# TopSide.net
KiCad netlist of a schematic drawn in Altium Designer
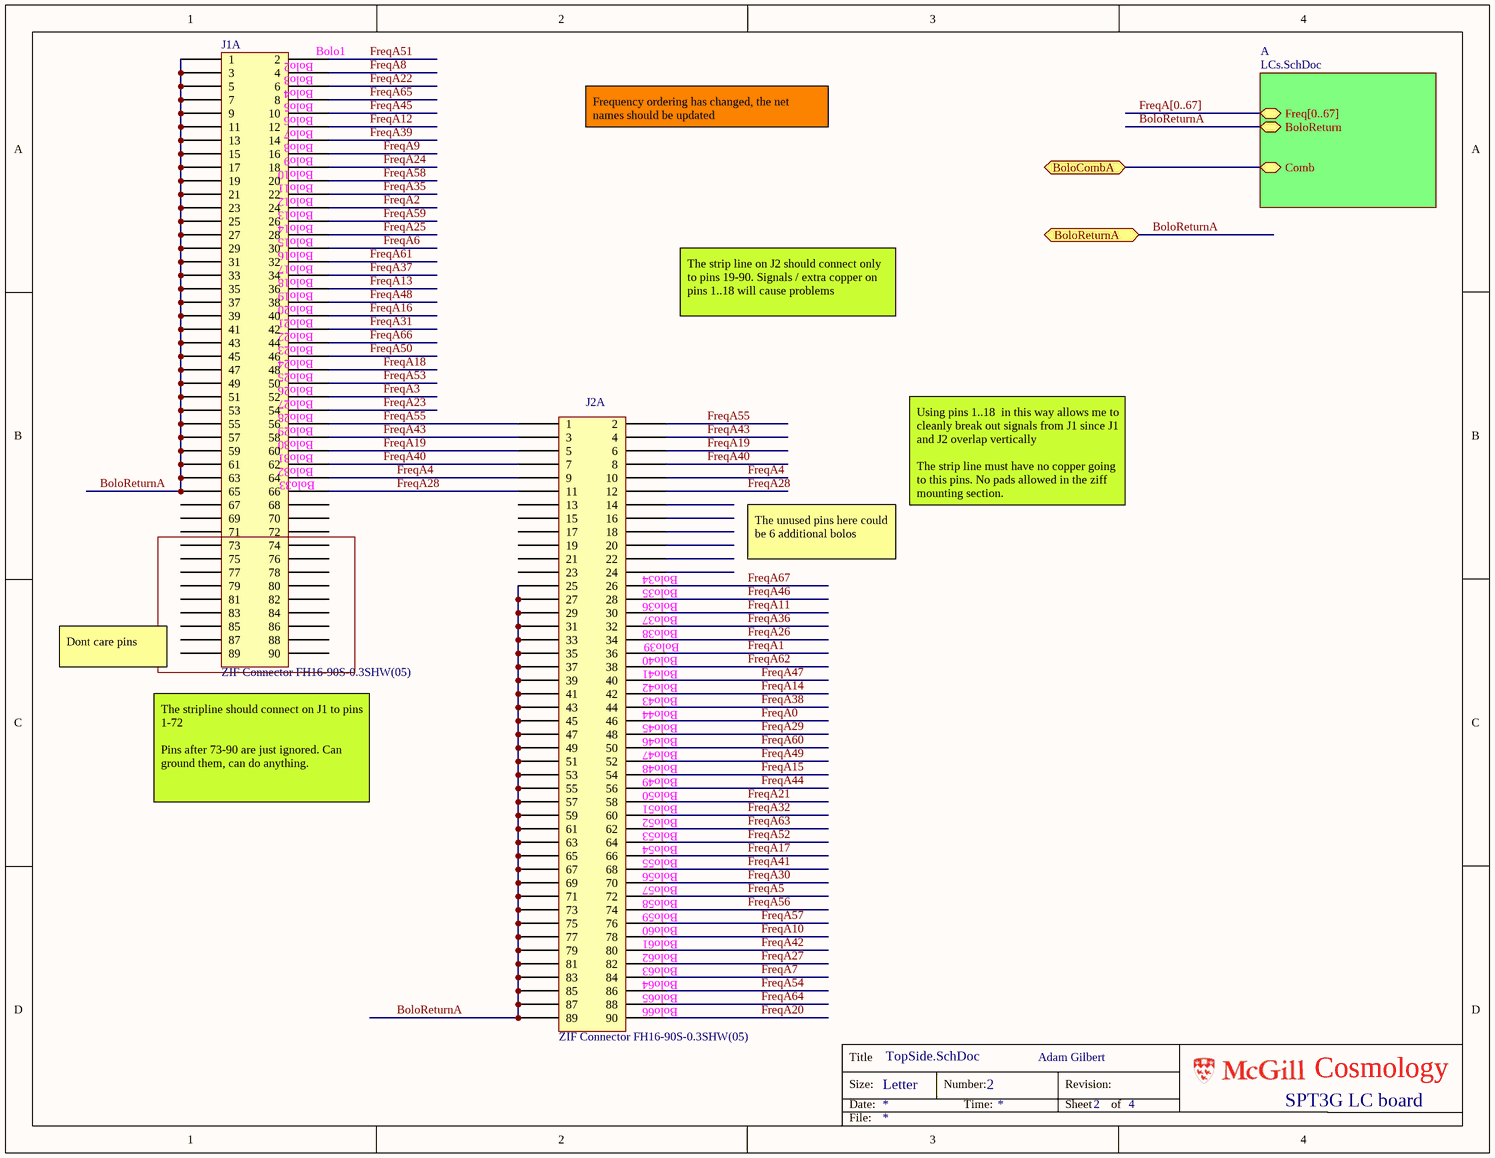
[diagram p0: TopSide.SchDoc]

(export (version "E")
  (design (tool "Eeschema 10.0.6"))
  (components
    (comp (ref "J1A")
      (value "ZIF Connector FH16-90S-0.3SHW(05)")
      (footprint "LCBoard_ZIFCon")
      (libsource (lib "SPT3G_LCBoard") (part "LCboard_FH16-90S-0.3SHW(05)"))
    )
    (comp (ref "J2A")
      (value "ZIF Connector FH16-90S-0.3SHW(05)")
      (footprint "LCBoard_ZIFCon")
      (libsource (lib "SPT3G_LCBoard") (part "LCboard_FH16-90S-0.3SHW(05)"))
    )
  )
  (nets
    (net (code "4") (name "/BoloReturnA") (class "Default")
      (node (ref "J1A") (pin "1") (pinfunction "1_1") (pintype "passive"))
      (node (ref "J1A") (pin "11") (pinfunction "11_11") (pintype "passive"))
      (node (ref "J1A") (pin "13") (pinfunction "13_13") (pintype "passive"))
      (node (ref "J1A") (pin "15") (pinfunction "15_15") (pintype "passive"))
      (node (ref "J1A") (pin "17") (pinfunction "17_17") (pintype "passive"))
      (node (ref "J1A") (pin "19") (pinfunction "19_19") (pintype "passive"))
      (node (ref "J1A") (pin "21") (pinfunction "21_21") (pintype "passive"))
      (node (ref "J1A") (pin "23") (pinfunction "23_23") (pintype "passive"))
      (node (ref "J1A") (pin "25") (pinfunction "25_25") (pintype "passive"))
      (node (ref "J1A") (pin "27") (pinfunction "27_27") (pintype "passive"))
      (node (ref "J1A") (pin "29") (pinfunction "29_29") (pintype "passive"))
      (node (ref "J1A") (pin "3") (pinfunction "3_3") (pintype "passive"))
      (node (ref "J1A") (pin "31") (pinfunction "31_31") (pintype "passive"))
      (node (ref "J1A") (pin "33") (pinfunction "33_33") (pintype "passive"))
      (node (ref "J1A") (pin "35") (pinfunction "35_35") (pintype "passive"))
      (node (ref "J1A") (pin "37") (pinfunction "37_37") (pintype "passive"))
      (node (ref "J1A") (pin "39") (pinfunction "39_39") (pintype "passive"))
      (node (ref "J1A") (pin "41") (pinfunction "41_41") (pintype "passive"))
      (node (ref "J1A") (pin "43") (pinfunction "43_43") (pintype "passive"))
      (node (ref "J1A") (pin "45") (pinfunction "45_45") (pintype "passive"))
      (node (ref "J1A") (pin "47") (pinfunction "47_47") (pintype "passive"))
      (node (ref "J1A") (pin "49") (pinfunction "49_49") (pintype "passive"))
      (node (ref "J1A") (pin "5") (pinfunction "5_5") (pintype "passive"))
      (node (ref "J1A") (pin "51") (pinfunction "51_51") (pintype "passive"))
      (node (ref "J1A") (pin "53") (pinfunction "53_53") (pintype "passive"))
      (node (ref "J1A") (pin "55") (pinfunction "55_55") (pintype "passive"))
      (node (ref "J1A") (pin "57") (pinfunction "57_57") (pintype "passive"))
      (node (ref "J1A") (pin "59") (pinfunction "59_59") (pintype "passive"))
      (node (ref "J1A") (pin "61") (pinfunction "61_61") (pintype "passive"))
      (node (ref "J1A") (pin "63") (pinfunction "63_63") (pintype "passive"))
      (node (ref "J1A") (pin "65") (pinfunction "65_65") (pintype "passive"))
      (node (ref "J1A") (pin "7") (pinfunction "7_7") (pintype "passive"))
      (node (ref "J1A") (pin "9") (pinfunction "9_9") (pintype "passive"))
      (node (ref "J2A") (pin "25") (pinfunction "25_25") (pintype "passive"))
      (node (ref "J2A") (pin "27") (pinfunction "27_27") (pintype "passive"))
      (node (ref "J2A") (pin "29") (pinfunction "29_29") (pintype "passive"))
      (node (ref "J2A") (pin "31") (pinfunction "31_31") (pintype "passive"))
      (node (ref "J2A") (pin "33") (pinfunction "33_33") (pintype "passive"))
      (node (ref "J2A") (pin "35") (pinfunction "35_35") (pintype "passive"))
      (node (ref "J2A") (pin "37") (pinfunction "37_37") (pintype "passive"))
      (node (ref "J2A") (pin "39") (pinfunction "39_39") (pintype "passive"))
      (node (ref "J2A") (pin "41") (pinfunction "41_41") (pintype "passive"))
      (node (ref "J2A") (pin "43") (pinfunction "43_43") (pintype "passive"))
      (node (ref "J2A") (pin "45") (pinfunction "45_45") (pintype "passive"))
      (node (ref "J2A") (pin "47") (pinfunction "47_47") (pintype "passive"))
      (node (ref "J2A") (pin "49") (pinfunction "49_49") (pintype "passive"))
      (node (ref "J2A") (pin "51") (pinfunction "51_51") (pintype "passive"))
      (node (ref "J2A") (pin "53") (pinfunction "53_53") (pintype "passive"))
      (node (ref "J2A") (pin "55") (pinfunction "55_55") (pintype "passive"))
      (node (ref "J2A") (pin "57") (pinfunction "57_57") (pintype "passive"))
      (node (ref "J2A") (pin "59") (pinfunction "59_59") (pintype "passive"))
      (node (ref "J2A") (pin "61") (pinfunction "61_61") (pintype "passive"))
      (node (ref "J2A") (pin "63") (pinfunction "63_63") (pintype "passive"))
      (node (ref "J2A") (pin "65") (pinfunction "65_65") (pintype "passive"))
      (node (ref "J2A") (pin "67") (pinfunction "67_67") (pintype "passive"))
      (node (ref "J2A") (pin "69") (pinfunction "69_69") (pintype "passive"))
      (node (ref "J2A") (pin "71") (pinfunction "71_71") (pintype "passive"))
      (node (ref "J2A") (pin "73") (pinfunction "73_73") (pintype "passive"))
      (node (ref "J2A") (pin "75") (pinfunction "75_75") (pintype "passive"))
      (node (ref "J2A") (pin "77") (pinfunction "77_77") (pintype "passive"))
      (node (ref "J2A") (pin "79") (pinfunction "79_79") (pintype "passive"))
      (node (ref "J2A") (pin "81") (pinfunction "81_81") (pintype "passive"))
      (node (ref "J2A") (pin "83") (pinfunction "83_83") (pintype "passive"))
      (node (ref "J2A") (pin "85") (pinfunction "85_85") (pintype "passive"))
      (node (ref "J2A") (pin "87") (pinfunction "87_87") (pintype "passive"))
      (node (ref "J2A") (pin "89") (pinfunction "89_89") (pintype "passive"))
    )
    (net (code "5") (name "/FreqA0") (class "Default")
      (node (ref "J2A") (pin "46") (pinfunction "46_46") (pintype "passive"))
    )
    (net (code "6") (name "/FreqA1") (class "Default")
      (node (ref "J2A") (pin "36") (pinfunction "36_36") (pintype "passive"))
    )
    (net (code "7") (name "/FreqA2") (class "Default")
      (node (ref "J1A") (pin "24") (pinfunction "24_24") (pintype "passive"))
    )
    (net (code "8") (name "/FreqA3") (class "Default")
      (node (ref "J1A") (pin "52") (pinfunction "52_52") (pintype "passive"))
    )
    (net (code "9") (name "/FreqA4") (class "Default")
      (node (ref "J1A") (pin "64") (pinfunction "64_64") (pintype "passive"))
      (node (ref "J2A") (pin "10") (pinfunction "10_10") (pintype "passive"))
      (node (ref "J2A") (pin "9") (pinfunction "9_9") (pintype "passive"))
    )
    (net (code "10") (name "/FreqA5") (class "Default")
      (node (ref "J2A") (pin "72") (pinfunction "72_72") (pintype "passive"))
    )
    (net (code "11") (name "/FreqA6") (class "Default")
      (node (ref "J1A") (pin "30") (pinfunction "30_30") (pintype "passive"))
    )
    (net (code "12") (name "/FreqA7") (class "Default")
      (node (ref "J2A") (pin "84") (pinfunction "84_84") (pintype "passive"))
    )
    (net (code "13") (name "/FreqA8") (class "Default")
      (node (ref "J1A") (pin "4") (pinfunction "4_4") (pintype "passive"))
    )
    (net (code "14") (name "/FreqA9") (class "Default")
      (node (ref "J1A") (pin "16") (pinfunction "16_16") (pintype "passive"))
    )
    (net (code "15") (name "/FreqA10") (class "Default")
      (node (ref "J2A") (pin "78") (pinfunction "78_78") (pintype "passive"))
    )
    (net (code "16") (name "/FreqA11") (class "Default")
      (node (ref "J2A") (pin "30") (pinfunction "30_30") (pintype "passive"))
    )
    (net (code "17") (name "/FreqA12") (class "Default")
      (node (ref "J1A") (pin "12") (pinfunction "12_12") (pintype "passive"))
    )
    (net (code "18") (name "/FreqA13") (class "Default")
      (node (ref "J1A") (pin "36") (pinfunction "36_36") (pintype "passive"))
    )
    (net (code "19") (name "/FreqA14") (class "Default")
      (node (ref "J2A") (pin "42") (pinfunction "42_42") (pintype "passive"))
    )
    (net (code "20") (name "/FreqA15") (class "Default")
      (node (ref "J2A") (pin "54") (pinfunction "54_54") (pintype "passive"))
    )
    (net (code "21") (name "/FreqA16") (class "Default")
      (node (ref "J1A") (pin "40") (pinfunction "40_40") (pintype "passive"))
    )
    (net (code "22") (name "/FreqA17") (class "Default")
      (node (ref "J2A") (pin "66") (pinfunction "66_66") (pintype "passive"))
    )
    (net (code "23") (name "/FreqA18") (class "Default")
      (node (ref "J1A") (pin "48") (pinfunction "48_48") (pintype "passive"))
    )
    (net (code "24") (name "/FreqA19") (class "Default")
      (node (ref "J1A") (pin "60") (pinfunction "60_60") (pintype "passive"))
      (node (ref "J2A") (pin "5") (pinfunction "5_5") (pintype "passive"))
      (node (ref "J2A") (pin "6") (pinfunction "6_6") (pintype "passive"))
    )
    (net (code "25") (name "/FreqA20") (class "Default")
      (node (ref "J2A") (pin "90") (pinfunction "90_90") (pintype "passive"))
    )
    (net (code "26") (name "/FreqA21") (class "Default")
      (node (ref "J2A") (pin "58") (pinfunction "58_58") (pintype "passive"))
    )
    (net (code "27") (name "/FreqA22") (class "Default")
      (node (ref "J1A") (pin "6") (pinfunction "6_6") (pintype "passive"))
    )
    (net (code "28") (name "/FreqA23") (class "Default")
      (node (ref "J1A") (pin "54") (pinfunction "54_54") (pintype "passive"))
    )
    (net (code "29") (name "/FreqA24") (class "Default")
      (node (ref "J1A") (pin "18") (pinfunction "18_18") (pintype "passive"))
    )
    (net (code "30") (name "/FreqA25") (class "Default")
      (node (ref "J1A") (pin "28") (pinfunction "28_28") (pintype "passive"))
    )
    (net (code "31") (name "/FreqA26") (class "Default")
      (node (ref "J2A") (pin "34") (pinfunction "34_34") (pintype "passive"))
    )
    (net (code "32") (name "/FreqA27") (class "Default")
      (node (ref "J2A") (pin "82") (pinfunction "82_82") (pintype "passive"))
    )
    (net (code "33") (name "/FreqA28") (class "Default")
      (node (ref "J1A") (pin "66") (pinfunction "66_66") (pintype "passive"))
      (node (ref "J2A") (pin "11") (pinfunction "11_11") (pintype "passive"))
      (node (ref "J2A") (pin "12") (pinfunction "12_12") (pintype "passive"))
    )
    (net (code "34") (name "/FreqA29") (class "Default")
      (node (ref "J2A") (pin "48") (pinfunction "48_48") (pintype "passive"))
    )
    (net (code "35") (name "/FreqA30") (class "Default")
      (node (ref "J2A") (pin "70") (pinfunction "70_70") (pintype "passive"))
    )
    (net (code "36") (name "/FreqA31") (class "Default")
      (node (ref "J1A") (pin "42") (pinfunction "42_42") (pintype "passive"))
    )
    (net (code "37") (name "/FreqA32") (class "Default")
      (node (ref "J2A") (pin "60") (pinfunction "60_60") (pintype "passive"))
    )
    (net (code "38") (name "/FreqA35") (class "Default")
      (node (ref "J1A") (pin "22") (pinfunction "22_22") (pintype "passive"))
    )
    (net (code "39") (name "/FreqA36") (class "Default")
      (node (ref "J2A") (pin "32") (pinfunction "32_32") (pintype "passive"))
    )
    (net (code "40") (name "/FreqA37") (class "Default")
      (node (ref "J1A") (pin "34") (pinfunction "34_34") (pintype "passive"))
    )
    (net (code "41") (name "/FreqA38") (class "Default")
      (node (ref "J2A") (pin "44") (pinfunction "44_44") (pintype "passive"))
    )
    (net (code "42") (name "/FreqA39") (class "Default")
      (node (ref "J1A") (pin "14") (pinfunction "14_14") (pintype "passive"))
    )
    (net (code "43") (name "/FreqA40") (class "Default")
      (node (ref "J1A") (pin "62") (pinfunction "62_62") (pintype "passive"))
      (node (ref "J2A") (pin "7") (pinfunction "7_7") (pintype "passive"))
      (node (ref "J2A") (pin "8") (pinfunction "8_8") (pintype "passive"))
    )
    (net (code "44") (name "/FreqA41") (class "Default")
      (node (ref "J2A") (pin "68") (pinfunction "68_68") (pintype "passive"))
    )
    (net (code "45") (name "/FreqA42") (class "Default")
      (node (ref "J2A") (pin "80") (pinfunction "80_80") (pintype "passive"))
    )
    (net (code "46") (name "/FreqA43") (class "Default")
      (node (ref "J1A") (pin "58") (pinfunction "58_58") (pintype "passive"))
      (node (ref "J2A") (pin "3") (pinfunction "3_3") (pintype "passive"))
      (node (ref "J2A") (pin "4") (pinfunction "4_4") (pintype "passive"))
    )
    (net (code "47") (name "/FreqA44") (class "Default")
      (node (ref "J2A") (pin "56") (pinfunction "56_56") (pintype "passive"))
    )
    (net (code "48") (name "/FreqA45") (class "Default")
      (node (ref "J1A") (pin "10") (pinfunction "10_10") (pintype "passive"))
    )
    (net (code "49") (name "/FreqA46") (class "Default")
      (node (ref "J2A") (pin "28") (pinfunction "28_28") (pintype "passive"))
    )
    (net (code "50") (name "/FreqA47") (class "Default")
      (node (ref "J2A") (pin "40") (pinfunction "40_40") (pintype "passive"))
    )
    (net (code "51") (name "/FreqA48") (class "Default")
      (node (ref "J1A") (pin "38") (pinfunction "38_38") (pintype "passive"))
    )
    (net (code "52") (name "/FreqA49") (class "Default")
      (node (ref "J2A") (pin "52") (pinfunction "52_52") (pintype "passive"))
    )
    (net (code "53") (name "/FreqA50") (class "Default")
      (node (ref "J1A") (pin "46") (pinfunction "46_46") (pintype "passive"))
    )
    (net (code "54") (name "/FreqA51") (class "Default")
      (node (ref "J1A") (pin "2") (pinfunction "2_2") (pintype "passive"))
    )
    (net (code "55") (name "/FreqA52") (class "Default")
      (node (ref "J2A") (pin "64") (pinfunction "64_64") (pintype "passive"))
    )
    (net (code "56") (name "/FreqA53") (class "Default")
      (node (ref "J1A") (pin "50") (pinfunction "50_50") (pintype "passive"))
    )
    (net (code "57") (name "/FreqA54") (class "Default")
      (node (ref "J2A") (pin "86") (pinfunction "86_86") (pintype "passive"))
    )
    (net (code "58") (name "/FreqA55") (class "Default")
      (node (ref "J1A") (pin "56") (pinfunction "56_56") (pintype "passive"))
      (node (ref "J2A") (pin "1") (pinfunction "1_1") (pintype "passive"))
      (node (ref "J2A") (pin "2") (pinfunction "2_2") (pintype "passive"))
    )
    (net (code "59") (name "/FreqA56") (class "Default")
      (node (ref "J2A") (pin "74") (pinfunction "74_74") (pintype "passive"))
    )
    (net (code "60") (name "/FreqA57") (class "Default")
      (node (ref "J2A") (pin "76") (pinfunction "76_76") (pintype "passive"))
    )
    (net (code "61") (name "/FreqA58") (class "Default")
      (node (ref "J1A") (pin "20") (pinfunction "20_20") (pintype "passive"))
    )
    (net (code "62") (name "/FreqA59") (class "Default")
      (node (ref "J1A") (pin "26") (pinfunction "26_26") (pintype "passive"))
    )
    (net (code "63") (name "/FreqA60") (class "Default")
      (node (ref "J2A") (pin "50") (pinfunction "50_50") (pintype "passive"))
    )
    (net (code "64") (name "/FreqA61") (class "Default")
      (node (ref "J1A") (pin "32") (pinfunction "32_32") (pintype "passive"))
    )
    (net (code "65") (name "/FreqA62") (class "Default")
      (node (ref "J2A") (pin "38") (pinfunction "38_38") (pintype "passive"))
    )
    (net (code "66") (name "/FreqA63") (class "Default")
      (node (ref "J2A") (pin "62") (pinfunction "62_62") (pintype "passive"))
    )
    (net (code "67") (name "/FreqA64") (class "Default")
      (node (ref "J2A") (pin "88") (pinfunction "88_88") (pintype "passive"))
    )
    (net (code "68") (name "/FreqA65") (class "Default")
      (node (ref "J1A") (pin "8") (pinfunction "8_8") (pintype "passive"))
    )
    (net (code "69") (name "/FreqA66") (class "Default")
      (node (ref "J1A") (pin "44") (pinfunction "44_44") (pintype "passive"))
    )
    (net (code "70") (name "/FreqA67") (class "Default")
      (node (ref "J2A") (pin "26") (pinfunction "26_26") (pintype "passive"))
    )
    (net (code "72") (name "unconnected-(J1A-Pad67)") (class "Default")
      (node (ref "J1A") (pin "67") (pinfunction "67_67") (pintype "passive"))
    )
    (net (code "73") (name "unconnected-(J1A-Pad68)") (class "Default")
      (node (ref "J1A") (pin "68") (pinfunction "68_68") (pintype "passive"))
    )
    (net (code "74") (name "unconnected-(J1A-Pad69)") (class "Default")
      (node (ref "J1A") (pin "69") (pinfunction "69_69") (pintype "passive"))
    )
    (net (code "75") (name "unconnected-(J1A-Pad70)") (class "Default")
      (node (ref "J1A") (pin "70") (pinfunction "70_70") (pintype "passive"))
    )
    (net (code "76") (name "unconnected-(J1A-Pad71)") (class "Default")
      (node (ref "J1A") (pin "71") (pinfunction "71_71") (pintype "passive"))
    )
    (net (code "77") (name "unconnected-(J1A-Pad72)") (class "Default")
      (node (ref "J1A") (pin "72") (pinfunction "72_72") (pintype "passive"))
    )
    (net (code "78") (name "unconnected-(J1A-Pad73)") (class "Default")
      (node (ref "J1A") (pin "73") (pinfunction "73_73") (pintype "passive"))
    )
    (net (code "79") (name "unconnected-(J1A-Pad74)") (class "Default")
      (node (ref "J1A") (pin "74") (pinfunction "74_74") (pintype "passive"))
    )
    (net (code "80") (name "unconnected-(J1A-Pad75)") (class "Default")
      (node (ref "J1A") (pin "75") (pinfunction "75_75") (pintype "passive"))
    )
    (net (code "81") (name "unconnected-(J1A-Pad76)") (class "Default")
      (node (ref "J1A") (pin "76") (pinfunction "76_76") (pintype "passive"))
    )
    (net (code "82") (name "unconnected-(J1A-Pad77)") (class "Default")
      (node (ref "J1A") (pin "77") (pinfunction "77_77") (pintype "passive"))
    )
    (net (code "83") (name "unconnected-(J1A-Pad78)") (class "Default")
      (node (ref "J1A") (pin "78") (pinfunction "78_78") (pintype "passive"))
    )
    (net (code "84") (name "unconnected-(J1A-Pad79)") (class "Default")
      (node (ref "J1A") (pin "79") (pinfunction "79_79") (pintype "passive"))
    )
    (net (code "85") (name "unconnected-(J1A-Pad80)") (class "Default")
      (node (ref "J1A") (pin "80") (pinfunction "80_80") (pintype "passive"))
    )
    (net (code "86") (name "unconnected-(J1A-Pad81)") (class "Default")
      (node (ref "J1A") (pin "81") (pinfunction "81_81") (pintype "passive"))
    )
    (net (code "87") (name "unconnected-(J1A-Pad82)") (class "Default")
      (node (ref "J1A") (pin "82") (pinfunction "82_82") (pintype "passive"))
    )
    (net (code "88") (name "unconnected-(J1A-Pad83)") (class "Default")
      (node (ref "J1A") (pin "83") (pinfunction "83_83") (pintype "passive"))
    )
    (net (code "89") (name "unconnected-(J1A-Pad84)") (class "Default")
      (node (ref "J1A") (pin "84") (pinfunction "84_84") (pintype "passive"))
    )
    (net (code "90") (name "unconnected-(J1A-Pad85)") (class "Default")
      (node (ref "J1A") (pin "85") (pinfunction "85_85") (pintype "passive"))
    )
    (net (code "91") (name "unconnected-(J1A-Pad86)") (class "Default")
      (node (ref "J1A") (pin "86") (pinfunction "86_86") (pintype "passive"))
    )
    (net (code "92") (name "unconnected-(J1A-Pad87)") (class "Default")
      (node (ref "J1A") (pin "87") (pinfunction "87_87") (pintype "passive"))
    )
    (net (code "93") (name "unconnected-(J1A-Pad88)") (class "Default")
      (node (ref "J1A") (pin "88") (pinfunction "88_88") (pintype "passive"))
    )
    (net (code "94") (name "unconnected-(J1A-Pad89)") (class "Default")
      (node (ref "J1A") (pin "89") (pinfunction "89_89") (pintype "passive"))
    )
    (net (code "95") (name "unconnected-(J1A-Pad90)") (class "Default")
      (node (ref "J1A") (pin "90") (pinfunction "90_90") (pintype "passive"))
    )
    (net (code "96") (name "unconnected-(J2A-Pad13)") (class "Default")
      (node (ref "J2A") (pin "13") (pinfunction "13_13") (pintype "passive"))
    )
    (net (code "97") (name "unconnected-(J2A-Pad14)") (class "Default")
      (node (ref "J2A") (pin "14") (pinfunction "14_14") (pintype "passive"))
    )
    (net (code "98") (name "unconnected-(J2A-Pad15)") (class "Default")
      (node (ref "J2A") (pin "15") (pinfunction "15_15") (pintype "passive"))
    )
    (net (code "99") (name "unconnected-(J2A-Pad16)") (class "Default")
      (node (ref "J2A") (pin "16") (pinfunction "16_16") (pintype "passive"))
    )
    (net (code "100") (name "unconnected-(J2A-Pad17)") (class "Default")
      (node (ref "J2A") (pin "17") (pinfunction "17_17") (pintype "passive"))
    )
    (net (code "101") (name "unconnected-(J2A-Pad18)") (class "Default")
      (node (ref "J2A") (pin "18") (pinfunction "18_18") (pintype "passive"))
    )
    (net (code "102") (name "unconnected-(J2A-Pad19)") (class "Default")
      (node (ref "J2A") (pin "19") (pinfunction "19_19") (pintype "passive"))
    )
    (net (code "103") (name "unconnected-(J2A-Pad20)") (class "Default")
      (node (ref "J2A") (pin "20") (pinfunction "20_20") (pintype "passive"))
    )
    (net (code "104") (name "unconnected-(J2A-Pad21)") (class "Default")
      (node (ref "J2A") (pin "21") (pinfunction "21_21") (pintype "passive"))
    )
    (net (code "105") (name "unconnected-(J2A-Pad22)") (class "Default")
      (node (ref "J2A") (pin "22") (pinfunction "22_22") (pintype "passive"))
    )
    (net (code "106") (name "unconnected-(J2A-Pad23)") (class "Default")
      (node (ref "J2A") (pin "23") (pinfunction "23_23") (pintype "passive"))
    )
    (net (code "107") (name "unconnected-(J2A-Pad24)") (class "Default")
      (node (ref "J2A") (pin "24") (pinfunction "24_24") (pintype "passive"))
    )
  )
)
